# MotorController.net
KiCad netlist of a schematic drawn in EAGLE
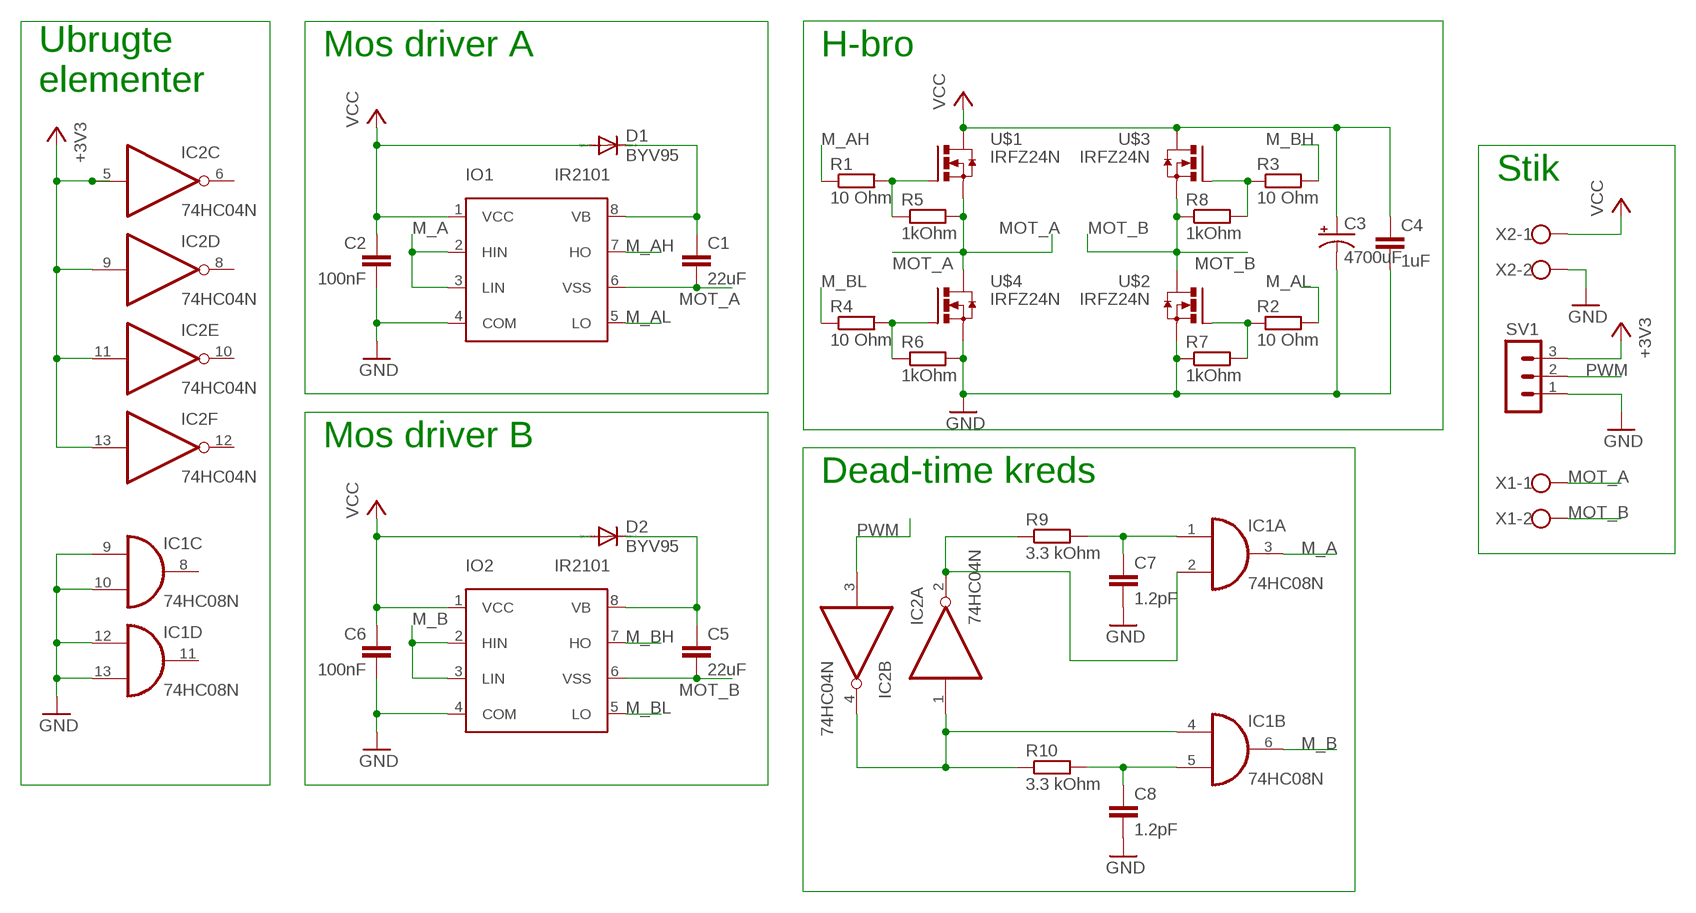
[diagram p0: schematic, sheet 1]

(export (version "E")
  (design (tool "Eeschema 10.0.6"))
  (components
    (comp (ref "C1")
      (value "22uF")
      (footprint "eagle-import:CAP-PTH-5MM")
      (libsource (lib "eagle-import") (part "CAPPTH1"))
    )
    (comp (ref "C2")
      (value "100nF")
      (footprint "eagle-import:CAP-PTH-5MM")
      (libsource (lib "eagle-import") (part "CAPPTH1"))
    )
    (comp (ref "C3")
      (value "4700uF")
      (footprint "eagle-import:CPOL-RADIAL-1000UF-25V")
      (libsource (lib "eagle-import") (part "CAP_POLPTH4"))
    )
    (comp (ref "C4")
      (value "1uF")
      (footprint "eagle-import:CAP-PTH-5MM")
      (libsource (lib "eagle-import") (part "CAPPTH1"))
    )
    (comp (ref "C5")
      (value "22uF")
      (footprint "eagle-import:CAP-PTH-5MM")
      (libsource (lib "eagle-import") (part "CAPPTH1"))
    )
    (comp (ref "C6")
      (value "100nF")
      (footprint "eagle-import:CAP-PTH-5MM")
      (libsource (lib "eagle-import") (part "CAPPTH1"))
    )
    (comp (ref "C7")
      (value "1.2pF")
      (footprint "eagle-import:CAP-PTH-5MM")
      (libsource (lib "eagle-import") (part "CAPPTH1"))
    )
    (comp (ref "C8")
      (value "1.2pF")
      (footprint "eagle-import:CAP-PTH-5MM")
      (libsource (lib "eagle-import") (part "CAPPTH1"))
    )
    (comp (ref "D1")
      (value "BYV95")
      (footprint "eagle-import:SOD57-10")
      (libsource (lib "eagle-import") (part "BYV95"))
    )
    (comp (ref "D2")
      (value "BYV95")
      (footprint "eagle-import:SOD57-10")
      (libsource (lib "eagle-import") (part "BYV95"))
    )
    (comp (ref "IC1")
      (value "74HC08N")
      (footprint "eagle-import:DIL14")
      (libsource (lib "eagle-import") (part "7408NHC"))
    )
    (comp (ref "IC2")
      (value "74HC04N")
      (footprint "eagle-import:DIL14")
      (libsource (lib "eagle-import") (part "7404NHC"))
    )
    (comp (ref "IO1")
      (value "IR2101")
      (footprint "eagle-import:DIL08")
      (libsource (lib "eagle-import") (part "IR2101"))
    )
    (comp (ref "IO2")
      (value "IR2101")
      (footprint "eagle-import:DIL08")
      (libsource (lib "eagle-import") (part "IR2101"))
    )
    (comp (ref "R1")
      (value "10 Ohm")
      (footprint "eagle-import:0207_10")
      (libsource (lib "eagle-import") (part "R-EU_0207/10"))
    )
    (comp (ref "R2")
      (value "10 Ohm")
      (footprint "eagle-import:0207_10")
      (libsource (lib "eagle-import") (part "R-EU_0207/10"))
    )
    (comp (ref "R3")
      (value "10 Ohm")
      (footprint "eagle-import:0207_10")
      (libsource (lib "eagle-import") (part "R-EU_0207/10"))
    )
    (comp (ref "R4")
      (value "10 Ohm")
      (footprint "eagle-import:0207_10")
      (libsource (lib "eagle-import") (part "R-EU_0207/10"))
    )
    (comp (ref "R5")
      (value "1kOhm")
      (footprint "eagle-import:0207_10")
      (libsource (lib "eagle-import") (part "R-EU_0207/10"))
    )
    (comp (ref "R6")
      (value "1kOhm")
      (footprint "eagle-import:0207_10")
      (libsource (lib "eagle-import") (part "R-EU_0207/10"))
    )
    (comp (ref "R7")
      (value "1kOhm")
      (footprint "eagle-import:0207_10")
      (libsource (lib "eagle-import") (part "R-EU_0207/10"))
    )
    (comp (ref "R8")
      (value "1kOhm")
      (footprint "eagle-import:0207_10")
      (libsource (lib "eagle-import") (part "R-EU_0207/10"))
    )
    (comp (ref "R9")
      (value "3.3 kOhm")
      (footprint "eagle-import:0207_10")
      (libsource (lib "eagle-import") (part "R-EU_0207/10"))
    )
    (comp (ref "R10")
      (value "3.3 kOhm")
      (footprint "eagle-import:0207_10")
      (libsource (lib "eagle-import") (part "R-EU_0207/10"))
    )
    (comp (ref "SV1")
      (value "MA03-1")
      (footprint "eagle-import:MA03-1")
      (libsource (lib "eagle-import") (part "MA03-1"))
    )
    (comp (ref "U$1")
      (value "IRFZ24N")
      (footprint "eagle-import:TO220BH")
      (libsource (lib "eagle-import") (part "IRFZ24N"))
    )
    (comp (ref "U$2")
      (value "IRFZ24N")
      (footprint "eagle-import:TO220BH")
      (libsource (lib "eagle-import") (part "IRFZ24N"))
    )
    (comp (ref "U$3")
      (value "IRFZ24N")
      (footprint "eagle-import:TO220BH")
      (libsource (lib "eagle-import") (part "IRFZ24N"))
    )
    (comp (ref "U$4")
      (value "IRFZ24N")
      (footprint "eagle-import:TO220BH")
      (libsource (lib "eagle-import") (part "IRFZ24N"))
    )
    (comp (ref "X1")
      (value "W237-102")
      (footprint "eagle-import:W237-102")
      (fields (field (name "MPN") "237-102"))
      (libsource (lib "eagle-import") (part "W237-102"))
    )
    (comp (ref "X2")
      (value "W237-102")
      (footprint "eagle-import:W237-102")
      (fields (field (name "MPN") "237-102"))
      (libsource (lib "eagle-import") (part "W237-102"))
    )
  )
  (nets
    (net (code "1") (name "+3V3") (class "Default")
      (node (ref "IC2") (pin "11") (pinfunction "I_11") (pintype "input"))
      (node (ref "IC2") (pin "13") (pinfunction "I_13") (pintype "input"))
      (node (ref "IC2") (pin "5") (pinfunction "I_5") (pintype "input"))
      (node (ref "IC2") (pin "9") (pinfunction "I_9") (pintype "input"))
      (node (ref "SV1") (pin "3") (pinfunction "3_3") (pintype "passive"))
    )
    (net (code "2") (name "/MOT_A") (class "Default")
      (node (ref "C1") (pin "2") (pinfunction "2_2") (pintype "passive"))
      (node (ref "IO1") (pin "6") (pinfunction "VSS_6") (pintype "bidirectional"))
      (node (ref "R5") (pin "2") (pinfunction "2_2") (pintype "passive"))
      (node (ref "U$1") (pin "S") (pinfunction "S_S") (pintype "passive"))
      (node (ref "U$4") (pin "D") (pinfunction "D_D") (pintype "passive"))
      (node (ref "X1") (pin "1") (pinfunction "KL_1") (pintype "passive"))
    )
    (net (code "3") (name "/MOT_B") (class "Default")
      (node (ref "C5") (pin "2") (pinfunction "2_2") (pintype "passive"))
      (node (ref "IO2") (pin "6") (pinfunction "VSS_6") (pintype "bidirectional"))
      (node (ref "R8") (pin "1") (pinfunction "1_1") (pintype "passive"))
      (node (ref "U$2") (pin "D") (pinfunction "D_D") (pintype "passive"))
      (node (ref "U$3") (pin "S") (pinfunction "S_S") (pintype "passive"))
      (node (ref "X1") (pin "2") (pinfunction "KL_2") (pintype "passive"))
    )
    (net (code "4") (name "/M_A") (class "Default")
      (node (ref "IC1") (pin "3") (pinfunction "O_3") (pintype "output"))
      (node (ref "IO1") (pin "2") (pinfunction "HIN_2") (pintype "bidirectional"))
      (node (ref "IO1") (pin "3") (pinfunction "LIN_3") (pintype "bidirectional"))
    )
    (net (code "5") (name "/M_AH") (class "Default")
      (node (ref "IO1") (pin "7") (pinfunction "HO_7") (pintype "bidirectional"))
      (node (ref "R1") (pin "1") (pinfunction "1_1") (pintype "passive"))
    )
    (net (code "6") (name "/M_AL") (class "Default")
      (node (ref "IO1") (pin "5") (pinfunction "LO_5") (pintype "bidirectional"))
      (node (ref "R2") (pin "2") (pinfunction "2_2") (pintype "passive"))
    )
    (net (code "7") (name "/M_B") (class "Default")
      (node (ref "IC1") (pin "6") (pinfunction "O_6") (pintype "output"))
      (node (ref "IO2") (pin "2") (pinfunction "HIN_2") (pintype "bidirectional"))
      (node (ref "IO2") (pin "3") (pinfunction "LIN_3") (pintype "bidirectional"))
    )
    (net (code "8") (name "/M_BH") (class "Default")
      (node (ref "IO2") (pin "7") (pinfunction "HO_7") (pintype "bidirectional"))
      (node (ref "R3") (pin "2") (pinfunction "2_2") (pintype "passive"))
    )
    (net (code "9") (name "/M_BL") (class "Default")
      (node (ref "IO2") (pin "5") (pinfunction "LO_5") (pintype "bidirectional"))
      (node (ref "R4") (pin "1") (pinfunction "1_1") (pintype "passive"))
    )
    (net (code "10") (name "/PWM") (class "Default")
      (node (ref "IC1") (pin "2") (pinfunction "I1_2") (pintype "input"))
      (node (ref "IC2") (pin "2") (pinfunction "O_2") (pintype "output"))
      (node (ref "IC2") (pin "3") (pinfunction "I_3") (pintype "input"))
      (node (ref "R9") (pin "1") (pinfunction "1_1") (pintype "passive"))
      (node (ref "SV1") (pin "2") (pinfunction "2_2") (pintype "passive"))
    )
    (net (code "11") (name "GND") (class "Default")
      (node (ref "C2") (pin "2") (pinfunction "2_2") (pintype "passive"))
      (node (ref "C3") (pin "2") (pinfunction "-_2") (pintype "passive"))
      (node (ref "C4") (pin "2") (pinfunction "2_2") (pintype "passive"))
      (node (ref "C6") (pin "2") (pinfunction "2_2") (pintype "passive"))
      (node (ref "C7") (pin "2") (pinfunction "2_2") (pintype "passive"))
      (node (ref "C8") (pin "2") (pinfunction "2_2") (pintype "passive"))
      (node (ref "IC1") (pin "10") (pinfunction "I1_10") (pintype "input"))
      (node (ref "IC1") (pin "12") (pinfunction "I0_12") (pintype "input"))
      (node (ref "IC1") (pin "13") (pinfunction "I1_13") (pintype "input"))
      (node (ref "IC1") (pin "9") (pinfunction "I0_9") (pintype "input"))
      (node (ref "IO1") (pin "4") (pinfunction "COM_4") (pintype "bidirectional"))
      (node (ref "IO2") (pin "4") (pinfunction "COM_4") (pintype "bidirectional"))
      (node (ref "R6") (pin "2") (pinfunction "2_2") (pintype "passive"))
      (node (ref "R7") (pin "1") (pinfunction "1_1") (pintype "passive"))
      (node (ref "SV1") (pin "1") (pinfunction "1_1") (pintype "passive"))
      (node (ref "U$2") (pin "S") (pinfunction "S_S") (pintype "passive"))
      (node (ref "U$4") (pin "S") (pinfunction "S_S") (pintype "passive"))
      (node (ref "X2") (pin "2") (pinfunction "KL_2") (pintype "passive"))
    )
    (net (code "12") (name "Net-(IC1A-I0)") (class "Default")
      (node (ref "C7") (pin "1") (pinfunction "1_1") (pintype "passive"))
      (node (ref "IC1") (pin "1") (pinfunction "I0_1") (pintype "input"))
      (node (ref "R9") (pin "2") (pinfunction "2_2") (pintype "passive"))
    )
    (net (code "13") (name "Net-(IC1B-I0)") (class "Default")
      (node (ref "IC1") (pin "4") (pinfunction "I0_4") (pintype "input"))
      (node (ref "IC2") (pin "1") (pinfunction "I_1") (pintype "input"))
      (node (ref "IC2") (pin "4") (pinfunction "O_4") (pintype "output"))
      (node (ref "R10") (pin "1") (pinfunction "1_1") (pintype "passive"))
    )
    (net (code "14") (name "Net-(IC1B-I1)") (class "Default")
      (node (ref "C8") (pin "1") (pinfunction "1_1") (pintype "passive"))
      (node (ref "IC1") (pin "5") (pinfunction "I1_5") (pintype "input"))
      (node (ref "R10") (pin "2") (pinfunction "2_2") (pintype "passive"))
    )
    (net (code "15") (name "Net-(IO1-VB)") (class "Default")
      (node (ref "C1") (pin "1") (pinfunction "1_1") (pintype "passive"))
      (node (ref "D1") (pin "C") (pinfunction "C_C") (pintype "passive"))
      (node (ref "IO1") (pin "8") (pinfunction "VB_8") (pintype "bidirectional"))
    )
    (net (code "16") (name "Net-(IO2-VB)") (class "Default")
      (node (ref "C5") (pin "1") (pinfunction "1_1") (pintype "passive"))
      (node (ref "D2") (pin "C") (pinfunction "C_C") (pintype "passive"))
      (node (ref "IO2") (pin "8") (pinfunction "VB_8") (pintype "bidirectional"))
    )
    (net (code "17") (name "Net-(R1-Pad2)") (class "Default")
      (node (ref "R1") (pin "2") (pinfunction "2_2") (pintype "passive"))
      (node (ref "R5") (pin "1") (pinfunction "1_1") (pintype "passive"))
      (node (ref "U$1") (pin "G") (pinfunction "G_G") (pintype "passive"))
    )
    (net (code "18") (name "Net-(R2-Pad1)") (class "Default")
      (node (ref "R2") (pin "1") (pinfunction "1_1") (pintype "passive"))
      (node (ref "R7") (pin "2") (pinfunction "2_2") (pintype "passive"))
      (node (ref "U$2") (pin "G") (pinfunction "G_G") (pintype "passive"))
    )
    (net (code "19") (name "Net-(R3-Pad1)") (class "Default")
      (node (ref "R3") (pin "1") (pinfunction "1_1") (pintype "passive"))
      (node (ref "R8") (pin "2") (pinfunction "2_2") (pintype "passive"))
      (node (ref "U$3") (pin "G") (pinfunction "G_G") (pintype "passive"))
    )
    (net (code "20") (name "Net-(R4-Pad2)") (class "Default")
      (node (ref "R4") (pin "2") (pinfunction "2_2") (pintype "passive"))
      (node (ref "R6") (pin "1") (pinfunction "1_1") (pintype "passive"))
      (node (ref "U$4") (pin "G") (pinfunction "G_G") (pintype "passive"))
    )
    (net (code "21") (name "VCC") (class "Default")
      (node (ref "C2") (pin "1") (pinfunction "1_1") (pintype "passive"))
      (node (ref "C3") (pin "1") (pinfunction "+_1") (pintype "passive"))
      (node (ref "C4") (pin "1") (pinfunction "1_1") (pintype "passive"))
      (node (ref "C6") (pin "1") (pinfunction "1_1") (pintype "passive"))
      (node (ref "D1") (pin "A") (pinfunction "A_A") (pintype "passive"))
      (node (ref "D2") (pin "A") (pinfunction "A_A") (pintype "passive"))
      (node (ref "IO1") (pin "1") (pinfunction "VCC_1") (pintype "bidirectional"))
      (node (ref "IO2") (pin "1") (pinfunction "VCC_1") (pintype "bidirectional"))
      (node (ref "U$1") (pin "D") (pinfunction "D_D") (pintype "passive"))
      (node (ref "U$3") (pin "D") (pinfunction "D_D") (pintype "passive"))
      (node (ref "X2") (pin "1") (pinfunction "KL_1") (pintype "passive"))
    )
    (net (code "22") (name "unconnected-(IC1C-O-Pad8)") (class "Default")
      (node (ref "IC1") (pin "8") (pinfunction "O_8") (pintype "output"))
    )
    (net (code "23") (name "unconnected-(IC1D-O-Pad11)") (class "Default")
      (node (ref "IC1") (pin "11") (pinfunction "O_11") (pintype "output"))
    )
    (net (code "24") (name "unconnected-(IC2C-O-Pad6)") (class "Default")
      (node (ref "IC2") (pin "6") (pinfunction "O_6") (pintype "output"))
    )
    (net (code "25") (name "unconnected-(IC2D-O-Pad8)") (class "Default")
      (node (ref "IC2") (pin "8") (pinfunction "O_8") (pintype "output"))
    )
    (net (code "26") (name "unconnected-(IC2E-O-Pad10)") (class "Default")
      (node (ref "IC2") (pin "10") (pinfunction "O_10") (pintype "output"))
    )
    (net (code "27") (name "unconnected-(IC2F-O-Pad12)") (class "Default")
      (node (ref "IC2") (pin "12") (pinfunction "O_12") (pintype "output"))
    )
  )
)
